# Atmega.net
KiCad netlist of a schematic drawn in Altium Designer
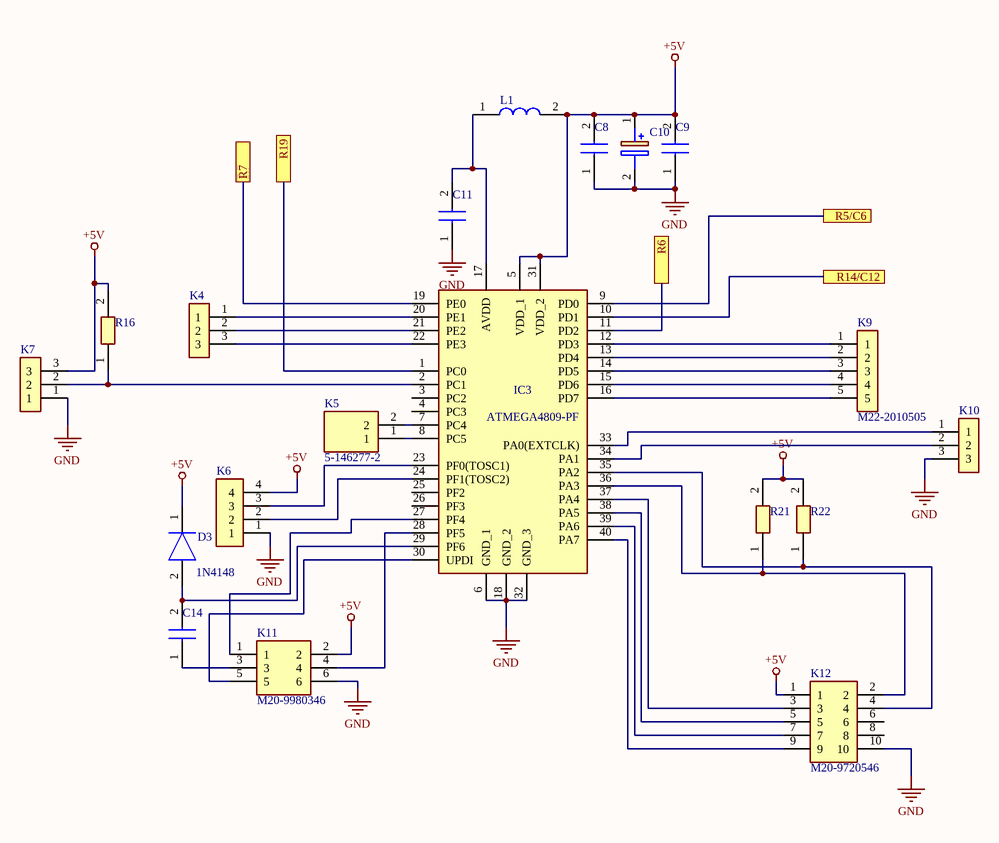
[diagram p0: Atmega.SchDoc]

(export (version "E")
  (design (tool "Eeschema 10.0.6"))
  (components
    (comp (ref "C8")
      (value "~")
      (footprint "SamacSys:CAPC2012X95N")
      (description "Capacitor")
      (fields (field (name "MANUFACTURER_PART_NUMBER") "CC0805KPX7R9BB104"))
      (libsource (lib "*") (part "CC0805KPX7R9BB104"))
    )
    (comp (ref "C9")
      (value "~")
      (footprint "SamacSys:CAPC2012X95N")
      (description "Capacitor")
      (fields (field (name "MANUFACTURER_PART_NUMBER") "CC0805KPX7R9BB104"))
      (libsource (lib "*") (part "CC0805KPX7R9BB104"))
    )
    (comp (ref "C10")
      (value "10µ")
      (footprint "SamacSys:CAPPRD200W52D500H1250")
      (description "Capacitor Polarised")
      (fields
        (field (name "MANUFACTURER_PART_NUMBER") "860010672009")
        (field (name "MOUSER PART NUMBER") "710-860010672009")
      )
      (libsource (lib "*") (part "860010672009"))
    )
    (comp (ref "C11")
      (value "~")
      (footprint "SamacSys:CAPC2012X95N")
      (description "Capacitor")
      (fields (field (name "MANUFACTURER_PART_NUMBER") "CC0805KPX7R9BB104"))
      (libsource (lib "*") (part "CC0805KPX7R9BB104"))
    )
    (comp (ref "C14")
      (value "~")
      (footprint "SamacSys:CAPC2012X95N")
      (description "Capacitor")
      (fields (field (name "MANUFACTURER_PART_NUMBER") "CC0805KPX7R9BB104"))
      (libsource (lib "*") (part "CC0805KPX7R9BB104"))
    )
    (comp (ref "D3")
      (value "1N4148")
      (footprint "SamacSys:1N4148WRHG")
      (description "Diode")
      (fields
        (field (name "MANUFACTURER_PART_NUMBER") "1N4148W RHG")
        (field (name "MOUSER PART NUMBER") "821-1N4148WRHG")
      )
      (libsource (lib "SoldeerBoutLib") (part "1N4148W_RHG"))
    )
    (comp (ref "IC3")
      (value "ATMEGA4809-PF")
      (footprint "SamacSys:DIP1543W58P254L5175H635Q40N")
      (description "Integrated Circuit")
      (fields (field (name "MOUSER PART NUMBER") "556-ATMEGA4809-PF"))
      (libsource (lib "SoldeerBoutLib") (part "ATMEGA4809-PF"))
    )
    (comp (ref "K4")
      (value "09-65-2038")
      (footprint "SamacSys:SHDR3W160P0X396_1X3_1112X1062X1425P")
      (description "Connector")
      (fields (field (name "MOUSER PART NUMBER") "538-09-65-2038"))
      (libsource (lib "SoldeerBoutLib") (part "09-65-2038"))
    )
    (comp (ref "K5")
      (value "5-146277-2")
      (footprint "SamacSys:HDRV2W67P0X254_1X2_467X234X823P")
      (description "Connector")
      (fields (field (name "MOUSER2 PART NUMBER") "571-5-146277-2"))
      (libsource (lib "*") (part "5-146277-2"))
    )
    (comp (ref "K6")
      (value "~")
      (footprint "SamacSys:HDRV4W64P0X254_1X4_1016X254X864P")
      (description "Connector")
      (fields (field (name "MANUFACTURER_PART_NUMBER") "M20-9990445"))
      (libsource (lib "SoldeerBoutLib") (part "M20-9990445"))
    )
    (comp (ref "K7")
      (value "~")
      (footprint "SamacSys:HDRV3W60P0X200_1X3_600X200X525P")
      (description "Connector")
      (fields
        (field (name "MOUSER2 PART NUMBER") "855-M22-2010305")
        (field (name "MANUFACTURER_PART_NUMBER") "M22-2010305")
      )
      (libsource (lib "SoldeerBoutLib") (part "M22-2010305"))
    )
    (comp (ref "K9")
      (value "M22-2010505")
      (footprint "SamacSys:HDRV5W50P0X200_1X5_1000X200X530P")
      (description "Connector")
      (libsource (lib "SoldeerBoutLib") (part "M22-2010505"))
    )
    (comp (ref "K10")
      (value "~")
      (footprint "SamacSys:HDRV3W60P0X200_1X3_600X200X525P")
      (description "Connector")
      (fields
        (field (name "MOUSER2 PART NUMBER") "855-M22-2010305")
        (field (name "MANUFACTURER_PART_NUMBER") "M22-2010305")
      )
      (libsource (lib "") (part "M22-2010305_1"))
    )
    (comp (ref "K11")
      (value "M20-9980346")
      (footprint "SamacSys:HDRV6W64P254_2X3_762X508X868P")
      (description "Connector")
      (fields (field (name "MOUSER2 PART NUMBER") "855-M20-9980346"))
      (libsource (lib "*") (part "M20-9980346"))
    )
    (comp (ref "K12")
      (value "M20-9720546")
      (footprint "SamacSys:HDRV10W64P254_2X5_1270X508X954P")
      (description "Connector")
      (libsource (lib "SoldeerBoutLib") (part "M20-9720546"))
    )
    (comp (ref "L1")
      (value "FDSD0518-H-100M=P3")
      (footprint "SamacSys:FDSD0518H100MP3")
      (description "Inductor")
      (libsource (lib "SoldeerBoutLib") (part "FDSD0518-H-100M=P3"))
    )
    (comp (ref "R16")
      (value "~")
      (footprint "SamacSys:RESC2012X90N")
      (description "Resistor")
      (fields (field (name "MANUFACTURER_PART_NUMBER") "CFN0805-JZ-R010ELF"))
      (libsource (lib "SoldeerBoutLib") (part "CFN0805-JZ-R010ELF"))
    )
    (comp (ref "R21")
      (value "~")
      (footprint "SamacSys:RESC2012X90N")
      (description "Resistor")
      (fields (field (name "MANUFACTURER_PART_NUMBER") "CFN0805-JZ-R010ELF"))
      (libsource (lib "SoldeerBoutLib") (part "CFN0805-JZ-R010ELF"))
    )
    (comp (ref "R22")
      (value "~")
      (footprint "SamacSys:RESC2012X90N")
      (description "Resistor")
      (fields (field (name "MANUFACTURER_PART_NUMBER") "CFN0805-JZ-R010ELF"))
      (libsource (lib "SoldeerBoutLib") (part "CFN0805-JZ-R010ELF"))
    )
  )
  (nets
    (net (code "1") (name "+5V") (class "Default")
      (node (ref "C10") (pin "1") (pinfunction "+_1") (pintype "passive"))
      (node (ref "C8") (pin "2") (pinfunction "2_2") (pintype "passive"))
      (node (ref "C9") (pin "2") (pinfunction "2_2") (pintype "passive"))
      (node (ref "D3") (pin "1") (pinfunction "K_1") (pintype "passive"))
      (node (ref "IC3") (pin "31") (pinfunction "VDD_2_31") (pintype "passive"))
      (node (ref "IC3") (pin "5") (pinfunction "VDD_1_5") (pintype "passive"))
      (node (ref "K11") (pin "2") (pinfunction "2_2") (pintype "passive"))
      (node (ref "K12") (pin "1") (pinfunction "1_1") (pintype "passive"))
      (node (ref "K6") (pin "4") (pinfunction "4_4") (pintype "passive"))
      (node (ref "K7") (pin "3") (pinfunction "3_3") (pintype "passive"))
      (node (ref "L1") (pin "2") (pinfunction "2_2") (pintype "passive"))
      (node (ref "R16") (pin "2") (pinfunction "2_2") (pintype "passive"))
      (node (ref "R21") (pin "2") (pinfunction "2_2") (pintype "passive"))
      (node (ref "R22") (pin "2") (pinfunction "2_2") (pintype "passive"))
    )
    (net (code "2") (name "/R5{slash}C6") (class "Default")
      (node (ref "IC3") (pin "9") (pinfunction "PD0_9") (pintype "passive"))
    )
    (net (code "3") (name "/R6") (class "Default")
      (node (ref "IC3") (pin "11") (pinfunction "PD2_11") (pintype "passive"))
    )
    (net (code "4") (name "/R7") (class "Default")
      (node (ref "IC3") (pin "19") (pinfunction "PE0_19") (pintype "passive"))
    )
    (net (code "5") (name "/R14{slash}C12") (class "Default")
      (node (ref "IC3") (pin "10") (pinfunction "PD1_10") (pintype "passive"))
    )
    (net (code "6") (name "/R19") (class "Default")
      (node (ref "IC3") (pin "1") (pinfunction "PC0_1") (pintype "passive"))
    )
    (net (code "7") (name "GND") (class "Default")
      (node (ref "C10") (pin "2") (pinfunction "-_2") (pintype "passive"))
      (node (ref "C11") (pin "1") (pinfunction "1_1") (pintype "passive"))
      (node (ref "C8") (pin "1") (pinfunction "1_1") (pintype "passive"))
      (node (ref "C9") (pin "1") (pinfunction "1_1") (pintype "passive"))
      (node (ref "IC3") (pin "18") (pinfunction "GND_2_18") (pintype "passive"))
      (node (ref "IC3") (pin "32") (pinfunction "GND_3_32") (pintype "passive"))
      (node (ref "IC3") (pin "6") (pinfunction "GND_1_6") (pintype "passive"))
      (node (ref "K10") (pin "3") (pinfunction "3_3") (pintype "passive"))
      (node (ref "K11") (pin "6") (pinfunction "6_6") (pintype "passive"))
      (node (ref "K12") (pin "10") (pinfunction "10_10") (pintype "passive"))
      (node (ref "K6") (pin "1") (pinfunction "1_1") (pintype "passive"))
      (node (ref "K7") (pin "1") (pinfunction "1_1") (pintype "passive"))
    )
    (net (code "8") (name "Net-(C14-Pad1)") (class "Default")
      (node (ref "C14") (pin "1") (pinfunction "1_1") (pintype "passive"))
      (node (ref "K11") (pin "3") (pinfunction "3_3") (pintype "passive"))
    )
    (net (code "9") (name "Net-(D3-A)") (class "Default")
      (node (ref "C14") (pin "2") (pinfunction "2_2") (pintype "passive"))
      (node (ref "D3") (pin "2") (pinfunction "A_2") (pintype "passive"))
      (node (ref "IC3") (pin "29") (pinfunction "PF6_29") (pintype "passive"))
    )
    (net (code "10") (name "Net-(IC3-AVDD)") (class "Default")
      (node (ref "C11") (pin "2") (pinfunction "2_2") (pintype "passive"))
      (node (ref "IC3") (pin "17") (pinfunction "AVDD_17") (pintype "passive"))
      (node (ref "L1") (pin "1") (pinfunction "1_1") (pintype "passive"))
    )
    (net (code "11") (name "Net-(IC3-PA0(EXTCLK))") (class "Default")
      (node (ref "IC3") (pin "33") (pinfunction "PA0(EXTCLK)_33") (pintype "passive"))
      (node (ref "K10") (pin "1") (pinfunction "1_1") (pintype "passive"))
    )
    (net (code "12") (name "Net-(IC3-PA1)") (class "Default")
      (node (ref "IC3") (pin "34") (pinfunction "PA1_34") (pintype "passive"))
      (node (ref "K10") (pin "2") (pinfunction "2_2") (pintype "passive"))
    )
    (net (code "13") (name "Net-(IC3-PA2)") (class "Default")
      (node (ref "IC3") (pin "35") (pinfunction "PA2_35") (pintype "passive"))
      (node (ref "K12") (pin "4") (pinfunction "4_4") (pintype "passive"))
      (node (ref "R22") (pin "1") (pinfunction "1_1") (pintype "passive"))
    )
    (net (code "14") (name "Net-(IC3-PA3)") (class "Default")
      (node (ref "IC3") (pin "36") (pinfunction "PA3_36") (pintype "passive"))
      (node (ref "K12") (pin "2") (pinfunction "2_2") (pintype "passive"))
      (node (ref "R21") (pin "1") (pinfunction "1_1") (pintype "passive"))
    )
    (net (code "15") (name "Net-(IC3-PA4)") (class "Default")
      (node (ref "IC3") (pin "37") (pinfunction "PA4_37") (pintype "passive"))
      (node (ref "K12") (pin "3") (pinfunction "3_3") (pintype "passive"))
    )
    (net (code "16") (name "Net-(IC3-PA5)") (class "Default")
      (node (ref "IC3") (pin "38") (pinfunction "PA5_38") (pintype "passive"))
      (node (ref "K12") (pin "5") (pinfunction "5_5") (pintype "passive"))
    )
    (net (code "17") (name "Net-(IC3-PA6)") (class "Default")
      (node (ref "IC3") (pin "39") (pinfunction "PA6_39") (pintype "passive"))
      (node (ref "K12") (pin "7") (pinfunction "7_7") (pintype "passive"))
    )
    (net (code "18") (name "Net-(IC3-PA7)") (class "Default")
      (node (ref "IC3") (pin "40") (pinfunction "PA7_40") (pintype "passive"))
      (node (ref "K12") (pin "9") (pinfunction "9_9") (pintype "passive"))
    )
    (net (code "19") (name "Net-(IC3-PC1)") (class "Default")
      (node (ref "IC3") (pin "2") (pinfunction "PC1_2") (pintype "passive"))
      (node (ref "K7") (pin "2") (pinfunction "2_2") (pintype "passive"))
      (node (ref "R16") (pin "1") (pinfunction "1_1") (pintype "passive"))
    )
    (net (code "20") (name "Net-(IC3-PC4)") (class "Default")
      (node (ref "IC3") (pin "7") (pinfunction "PC4_7") (pintype "passive"))
      (node (ref "K5") (pin "2") (pinfunction "2_2") (pintype "passive"))
    )
    (net (code "21") (name "Net-(IC3-PC5)") (class "Default")
      (node (ref "IC3") (pin "8") (pinfunction "PC5_8") (pintype "passive"))
      (node (ref "K5") (pin "1") (pinfunction "1_1") (pintype "passive"))
    )
    (net (code "22") (name "Net-(IC3-PD3)") (class "Default")
      (node (ref "IC3") (pin "12") (pinfunction "PD3_12") (pintype "passive"))
      (node (ref "K9") (pin "1") (pinfunction "1_1") (pintype "passive"))
    )
    (net (code "23") (name "Net-(IC3-PD4)") (class "Default")
      (node (ref "IC3") (pin "13") (pinfunction "PD4_13") (pintype "passive"))
      (node (ref "K9") (pin "2") (pinfunction "2_2") (pintype "passive"))
    )
    (net (code "24") (name "Net-(IC3-PD5)") (class "Default")
      (node (ref "IC3") (pin "14") (pinfunction "PD5_14") (pintype "passive"))
      (node (ref "K9") (pin "3") (pinfunction "3_3") (pintype "passive"))
    )
    (net (code "25") (name "Net-(IC3-PD6)") (class "Default")
      (node (ref "IC3") (pin "15") (pinfunction "PD6_15") (pintype "passive"))
      (node (ref "K9") (pin "4") (pinfunction "4_4") (pintype "passive"))
    )
    (net (code "26") (name "Net-(IC3-PD7)") (class "Default")
      (node (ref "IC3") (pin "16") (pinfunction "PD7_16") (pintype "passive"))
      (node (ref "K9") (pin "5") (pinfunction "5_5") (pintype "passive"))
    )
    (net (code "27") (name "Net-(IC3-PE1)") (class "Default")
      (node (ref "IC3") (pin "20") (pinfunction "PE1_20") (pintype "passive"))
      (node (ref "K4") (pin "1") (pinfunction "1_1") (pintype "passive"))
    )
    (net (code "28") (name "Net-(IC3-PE2)") (class "Default")
      (node (ref "IC3") (pin "21") (pinfunction "PE2_21") (pintype "passive"))
      (node (ref "K4") (pin "2") (pinfunction "2_2") (pintype "passive"))
    )
    (net (code "29") (name "Net-(IC3-PE3)") (class "Default")
      (node (ref "IC3") (pin "22") (pinfunction "PE3_22") (pintype "passive"))
      (node (ref "K4") (pin "3") (pinfunction "3_3") (pintype "passive"))
    )
    (net (code "30") (name "Net-(IC3-PF0(TOSC1))") (class "Default")
      (node (ref "IC3") (pin "23") (pinfunction "PF0(TOSC1)_23") (pintype "passive"))
      (node (ref "K6") (pin "3") (pinfunction "3_3") (pintype "passive"))
    )
    (net (code "31") (name "Net-(IC3-PF1(TOSC2))") (class "Default")
      (node (ref "IC3") (pin "24") (pinfunction "PF1(TOSC2)_24") (pintype "passive"))
      (node (ref "K6") (pin "2") (pinfunction "2_2") (pintype "passive"))
    )
    (net (code "32") (name "Net-(IC3-PF4)") (class "Default")
      (node (ref "IC3") (pin "27") (pinfunction "PF4_27") (pintype "passive"))
      (node (ref "K11") (pin "1") (pinfunction "1_1") (pintype "passive"))
    )
    (net (code "33") (name "Net-(IC3-PF5)") (class "Default")
      (node (ref "IC3") (pin "28") (pinfunction "PF5_28") (pintype "passive"))
      (node (ref "K11") (pin "4") (pinfunction "4_4") (pintype "passive"))
    )
    (net (code "34") (name "Net-(IC3-UPDI)") (class "Default")
      (node (ref "IC3") (pin "30") (pinfunction "UPDI_30") (pintype "passive"))
      (node (ref "K11") (pin "5") (pinfunction "5_5") (pintype "passive"))
    )
    (net (code "35") (name "unconnected-(IC3-PC2-Pad3)") (class "Default")
      (node (ref "IC3") (pin "3") (pinfunction "PC2_3") (pintype "passive"))
    )
    (net (code "36") (name "unconnected-(IC3-PC3-Pad4)") (class "Default")
      (node (ref "IC3") (pin "4") (pinfunction "PC3_4") (pintype "passive"))
    )
    (net (code "37") (name "unconnected-(IC3-PF2-Pad25)") (class "Default")
      (node (ref "IC3") (pin "25") (pinfunction "PF2_25") (pintype "passive"))
    )
    (net (code "38") (name "unconnected-(IC3-PF3-Pad26)") (class "Default")
      (node (ref "IC3") (pin "26") (pinfunction "PF3_26") (pintype "passive"))
    )
    (net (code "39") (name "unconnected-(K12-Pad6)") (class "Default")
      (node (ref "K12") (pin "6") (pinfunction "6_6") (pintype "passive"))
    )
    (net (code "40") (name "unconnected-(K12-Pad8)") (class "Default")
      (node (ref "K12") (pin "8") (pinfunction "8_8") (pintype "passive"))
    )
  )
)
